# blum_SumoBRD_ECEN2440F24.net
KiCad netlist of a schematic drawn in Altium Designer
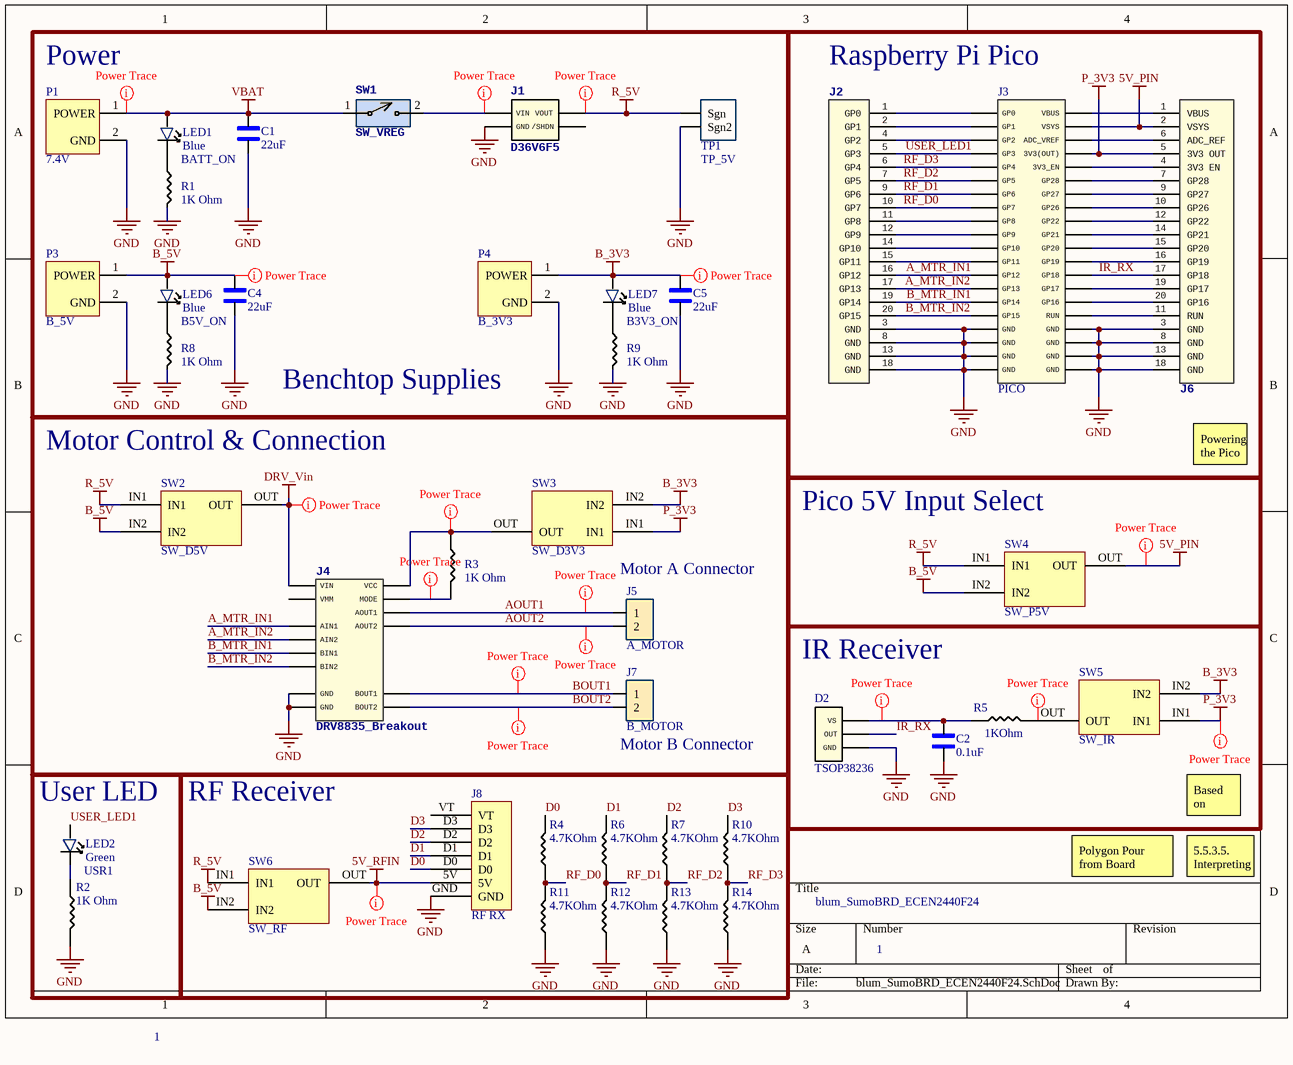
[diagram p0: blum_SumoBRD_ECEN2440F24.SchDoc]

(export (version "E")
  (design (tool "Eeschema 10.0.6"))
  (components
    (comp (ref "C1")
      (value "22uF")
      (footprint "1206_Passive_Capacitor")
      (description "22uF ±10% 25V X5R 1206 Multilayer Ceramic Capacitors MLCC - SMD/SMT RoHS")
      (fields (field (name "MFR PART #") "CL31A226KAHNNNE") (field (name "LCSC PART#") "C12891"))
      (libsource (lib "blum_SumoBRD_ECEN2440F24") (part "C_22uF_1206"))
    )
    (comp (ref "C2")
      (value "0.1uF")
      (footprint "1206_Passive_Capacitor")
      (description "MULTILAYER CERAMIC CAPACITORS MLCC - SMD/SMT 0.1UF 50V 1206 ROHS")
      (fields (field (name "MFR PART #") "CL31B104MBCNNNC") (field (name "LCSC PART#") "C730479"))
      (libsource (lib "blum_SumoBRD_ECEN2440F24") (part "C_0.1uF_1206"))
    )
    (comp (ref "C4")
      (value "22uF")
      (footprint "1206_Passive_Capacitor")
      (description "22uF ±10% 25V X5R 1206 Multilayer Ceramic Capacitors MLCC - SMD/SMT RoHS")
      (fields (field (name "MFR PART #") "CL31A226KAHNNNE") (field (name "LCSC PART#") "C12891"))
      (libsource (lib "blum_SumoBRD_ECEN2440F24") (part "C_22uF_1206"))
    )
    (comp (ref "C5")
      (value "22uF")
      (footprint "1206_Passive_Capacitor")
      (description "22uF ±10% 25V X5R 1206 Multilayer Ceramic Capacitors MLCC - SMD/SMT RoHS")
      (fields (field (name "MFR PART #") "CL31A226KAHNNNE") (field (name "LCSC PART#") "C12891"))
      (libsource (lib "blum_SumoBRD_ECEN2440F24") (part "C_22uF_1206"))
    )
    (comp (ref "D2")
      (value "TSOP38236")
      (footprint "D_TSOP38238")
      (description "IR Receiver, TSOP38236, 36 kHz")
      (libsource (lib "blum_SumoBRD_ECEN2440F24") (part "D_TSOP38238"))
    )
    (comp (ref "J1")
      (value "D36V6F5")
      (footprint "D36V6F5_JF_4")
      (description "5V, 600mA Step Down Voltage Regulator, D36V6F5. 2.54mm, P=2.54mm, Female Headers ROHS")
      (libsource (lib "blum_SumoBRD_ECEN2440F24") (part "D36V6F5_JF_4"))
    )
    (comp (ref "J2")
      (value "SAMTEC-SSQ-107-01-X-SJ")
      (footprint "JF-20-SSQ-1020-X")
      (description "2.54mm Brass Straight 1x7P 7 1 Straight,P=2.54mm  Female Headers ROHS")
      (fields (field (name "MFR PART #") "B-2200S07P-A120") (field (name "LCSC PART#") "C124418"))
      (libsource (lib "blum_SumoBRD_ECEN2440F24") (part "JF_20_PIN_FEMALE_L"))
    )
    (comp (ref "J3")
      (value "PICO")
      (footprint "RASPBERRY_PI_PICO")
      (libsource (lib "blum_SumoBRD_ECEN2440F24") (part "JF_RASPBERRY_PI_PICO"))
    )
    (comp (ref "J4")
      (value "DRV8835_Breakout")
      (footprint "JF_14_DRV8835")
      (description "Pololu DRV8835 Breakout Board\r\n2.54mm, P=2.54mm, Female Headers ROHS")
      (libsource (lib "blum_SumoBRD_ECEN2440F24") (part "DRV8835_JF_14"))
    )
    (comp (ref "J5")
      (value "A_MOTOR")
      (footprint "2_PIN_100MIL")
      (description "2.54mm Straight 2 1 Header，Breakaway Through Hole,P=2.54mm Pin Header & Female Header ROHS")
      (fields (field (name "LCSC PART#") "C124375") (field (name "MFR PART #") "B-2100S02P-A110"))
      (libsource (lib "blum_SumoBRD_ECEN2440F24") (part "JM_2_PIN_MALE"))
    )
    (comp (ref "J6")
      (value "SAMTEC-SSQ-107-01-X-SJ")
      (footprint "JF-20-SSQ-1020-X")
      (description "2.54mm Brass Straight 1x7P 7 1 Straight,P=2.54mm  Female Headers ROHS")
      (fields (field (name "MFR PART #") "B-2200S07P-A120") (field (name "LCSC PART#") "C124418"))
      (libsource (lib "blum_SumoBRD_ECEN2440F24") (part "JF_20_PIN_FEMALE_R"))
    )
    (comp (ref "J7")
      (value "B_MOTOR")
      (footprint "2_PIN_100MIL")
      (description "2.54mm Straight 2 1 Header，Breakaway Through Hole,P=2.54mm Pin Header & Female Header ROHS")
      (fields (field (name "LCSC PART#") "C124375") (field (name "MFR PART #") "B-2100S02P-A110"))
      (libsource (lib "blum_SumoBRD_ECEN2440F24") (part "JM_2_PIN_MALE_1"))
    )
    (comp (ref "J8")
      (value "RF RX")
      (footprint "JF_RF_Receiver")
      (description "RF Receiver, 7 pin")
      (libsource (lib "blum_SumoBRD_ECEN2440F24") (part "JF_RF_Receiver"))
    )
    (comp (ref "LED1")
      (value "BATT_ON")
      (footprint "LED_1206")
      (description "blue 1206  Light Emitting Diodes (LED) ROHS")
      (fields
        (field (name "MFR PART #") "NCD1206B1")
        (field (name "LCSC PART#") "C130717")
        (field (name "ALTIUM_VALUE") "Blue")
      )
      (libsource (lib "blum_SumoBRD_ECEN2440F24") (part "LED_BLUE_1206"))
    )
    (comp (ref "LED2")
      (value "USR1")
      (footprint "LED_1206")
      (description "Green 513~528nm 1206 Light Emitting Diodes (LED) RoHS")
      (fields
        (field (name "MFR PART #") "SZYY1206G")
        (field (name "LCSC PART#") "C434439")
        (field (name "ALTIUM_VALUE") "Green")
      )
      (libsource (lib "blum_SumoBRD_ECEN2440F24") (part "LED_GREEN_1206"))
    )
    (comp (ref "LED6")
      (value "B5V_ON")
      (footprint "LED_1206")
      (description "Benchtop Power Supply 5V output ON\r\nblue 1206  Light Emitting Diodes (LED) ROHS")
      (fields
        (field (name "MFR PART #") "NCD1206B1")
        (field (name "LCSC PART#") "C130717")
        (field (name "ALTIUM_VALUE") "Blue")
      )
      (libsource (lib "blum_SumoBRD_ECEN2440F24") (part "LED_BLUE_1206"))
    )
    (comp (ref "LED7")
      (value "B3V3_ON")
      (footprint "LED_1206")
      (description "Benchtop Power Supply 5V output ON\r\nblue 1206  Light Emitting Diodes (LED) ROHS")
      (fields
        (field (name "MFR PART #") "NCD1206B1")
        (field (name "LCSC PART#") "C130717")
        (field (name "ALTIUM_VALUE") "Blue")
      )
      (libsource (lib "blum_SumoBRD_ECEN2440F24") (part "LED_BLUE_1206"))
    )
    (comp (ref "P1")
      (value "7.4V")
      (footprint "P_JST_RCY")
      (description "JST RCY for LiPO battery")
      (libsource (lib "blum_SumoBRD_ECEN2440F24") (part "P_JST_RCY"))
    )
    (comp (ref "P3")
      (value "B_5V")
      (footprint "P_Terminal block 3.5mm-pitch")
      (description "Benchtop Power Supply: 5V \r\nGreen Straight pin 3.5mm  pitch; P=3.5mm  Screw terminal ROHS")
      (fields (field (name "MFR PART #") "KF350-3.5-2P") (field (name "MANUFACTURER") "Cixi Kefa Elec"))
      (libsource (lib "blum_SumoBRD_ECEN2440F24") (part "P_Terminal block"))
    )
    (comp (ref "P4")
      (value "B_3V3")
      (footprint "P_Terminal block 3.5mm-pitch")
      (description "Benchtop Power Supply: 3V3\r\nGreen Straight pin 3.5mm  pitch; P=3.5mm  Screw terminal ROHS")
      (fields (field (name "MFR PART #") "KF350-3.5-2P") (field (name "MANUFACTURER") "Cixi Kefa Elec"))
      (libsource (lib "blum_SumoBRD_ECEN2440F24") (part "P_Terminal block"))
    )
    (comp (ref "R1")
      (value "1K Ohm")
      (footprint "1206_Passive_Resitor")
      (description "CHIP RESISTOR - SURFACE MOUNT 1KOHMS ±1% 1/4W 1206 ROHS")
      (fields (field (name "MFR PART #") "RNCP1206FTD1K00CT") (field (name "LCSC PART#") "C4410"))
      (libsource (lib "blum_SumoBRD_ECEN2440F24") (part "R_1K_1206"))
    )
    (comp (ref "R2")
      (value "1K Ohm")
      (footprint "1206_Passive_Resitor")
      (description "CHIP RESISTOR - SURFACE MOUNT 1KOHMS ±1% 1/4W 1206 ROHS")
      (fields (field (name "MFR PART #") "RNCP1206FTD1K00CT") (field (name "LCSC PART#") "C4410"))
      (libsource (lib "blum_SumoBRD_ECEN2440F24") (part "R_1K_1206"))
    )
    (comp (ref "R3")
      (value "1K Ohm")
      (footprint "1206_Passive_Resitor")
      (description "CHIP RESISTOR - SURFACE MOUNT 1KOHMS ±1% 1/4W 1206 ROHS")
      (fields (field (name "MFR PART #") "RNCP1206FTD1K00CT") (field (name "LCSC PART#") "C4410"))
      (libsource (lib "blum_ECEN2440_sumo_new") (part "R_1K_1206"))
    )
    (comp (ref "R4")
      (value "4.7KOhm")
      (footprint "1206_Passive_Resitor")
      (description "4.7kΩ ±1% 0.25W ±100ppm/℃ 1206 Chip Resistor - Surface Mount RoHS")
      (fields (field (name "LCSC PART#") "C17936") (field (name "MFR PART #") "1206W4F4701T5E"))
      (libsource (lib "blum_SumoBRD_ECEN2440F24") (part "R_4.7k_1206"))
    )
    (comp (ref "R5")
      (value "1KOhm")
      (footprint "1206_Passive_Resitor")
      (description "10 kOhms ±5% 0.25W, 1/4W Chip Resistor 1206 (3216 Metric) Automotive AEC-Q200 Thick Film")
      (fields (field (name "MFR PART #") "RMCF1206FT10K0") (field (name "LCSC PART#") "C17902"))
      (libsource (lib "blum_SumoBRD_ECEN2440F24") (part "R_10KOhm_1206"))
    )
    (comp (ref "R6")
      (value "4.7KOhm")
      (footprint "1206_Passive_Resitor")
      (description "4.7kΩ ±1% 0.25W ±100ppm/℃ 1206 Chip Resistor - Surface Mount RoHS")
      (fields (field (name "LCSC PART#") "C17936") (field (name "MFR PART #") "1206W4F4701T5E"))
      (libsource (lib "blum_SumoBRD_ECEN2440F24") (part "R_4.7k_1206"))
    )
    (comp (ref "R7")
      (value "4.7KOhm")
      (footprint "1206_Passive_Resitor")
      (description "4.7kΩ ±1% 0.25W ±100ppm/℃ 1206 Chip Resistor - Surface Mount RoHS")
      (fields (field (name "LCSC PART#") "C17936") (field (name "MFR PART #") "1206W4F4701T5E"))
      (libsource (lib "blum_SumoBRD_ECEN2440F24") (part "R_4.7k_1206"))
    )
    (comp (ref "R8")
      (value "1K Ohm")
      (footprint "1206_Passive_Resitor")
      (description "CHIP RESISTOR - SURFACE MOUNT 1KOHMS ±1% 1/4W 1206 ROHS")
      (fields (field (name "MFR PART #") "RNCP1206FTD1K00CT") (field (name "LCSC PART#") "C4410"))
      (libsource (lib "blum_SumoBRD_ECEN2440F24") (part "R_1K_1206"))
    )
    (comp (ref "R9")
      (value "1K Ohm")
      (footprint "1206_Passive_Resitor")
      (description "CHIP RESISTOR - SURFACE MOUNT 1KOHMS ±1% 1/4W 1206 ROHS")
      (fields (field (name "MFR PART #") "RNCP1206FTD1K00CT") (field (name "LCSC PART#") "C4410"))
      (libsource (lib "blum_SumoBRD_ECEN2440F24") (part "R_1K_1206"))
    )
    (comp (ref "R10")
      (value "4.7KOhm")
      (footprint "1206_Passive_Resitor")
      (description "4.7kΩ ±1% 0.25W ±100ppm/℃ 1206 Chip Resistor - Surface Mount RoHS")
      (fields (field (name "LCSC PART#") "C17936") (field (name "MFR PART #") "1206W4F4701T5E"))
      (libsource (lib "blum_SumoBRD_ECEN2440F24") (part "R_4.7k_1206"))
    )
    (comp (ref "R11")
      (value "4.7KOhm")
      (footprint "1206_Passive_Resitor")
      (description "4.7kΩ ±1% 0.25W ±100ppm/℃ 1206 Chip Resistor - Surface Mount RoHS")
      (fields (field (name "LCSC PART#") "C17936") (field (name "MFR PART #") "1206W4F4701T5E"))
      (libsource (lib "blum_SumoBRD_ECEN2440F24") (part "R_4.7k_1206"))
    )
    (comp (ref "R12")
      (value "4.7KOhm")
      (footprint "1206_Passive_Resitor")
      (description "4.7kΩ ±1% 0.25W ±100ppm/℃ 1206 Chip Resistor - Surface Mount RoHS")
      (fields (field (name "LCSC PART#") "C17936") (field (name "MFR PART #") "1206W4F4701T5E"))
      (libsource (lib "blum_SumoBRD_ECEN2440F24") (part "R_4.7k_1206"))
    )
    (comp (ref "R13")
      (value "4.7KOhm")
      (footprint "1206_Passive_Resitor")
      (description "4.7kΩ ±1% 0.25W ±100ppm/℃ 1206 Chip Resistor - Surface Mount RoHS")
      (fields (field (name "LCSC PART#") "C17936") (field (name "MFR PART #") "1206W4F4701T5E"))
      (libsource (lib "blum_SumoBRD_ECEN2440F24") (part "R_4.7k_1206"))
    )
    (comp (ref "R14")
      (value "4.7KOhm")
      (footprint "1206_Passive_Resitor")
      (description "4.7kΩ ±1% 0.25W ±100ppm/℃ 1206 Chip Resistor - Surface Mount RoHS")
      (fields (field (name "LCSC PART#") "C17936") (field (name "MFR PART #") "1206W4F4701T5E"))
      (libsource (lib "blum_SumoBRD_ECEN2440F24") (part "R_4.7k_1206"))
    )
    (comp (ref "SW1")
      (value "SW_VREG")
      (footprint "2Pin-Header-Conn")
      (description "2Pin Header")
      (fields (field (name "LCSC PART#") "C124375"))
      (libsource (lib "blum_SumoBRD_ECEN2440F24") (part "SW_2Pin_100mil_Switch"))
    )
    (comp (ref "SW2")
      (value "SW_D5V")
      (footprint "3PIN_SWITCH")
      (description "3Pin Header")
      (libsource (lib "blum_SumoBRD_ECEN2440F24") (part "SW_3Pin"))
    )
    (comp (ref "SW3")
      (value "SW_D3V3")
      (footprint "3PIN_SWITCH")
      (description "3Pin Header")
      (libsource (lib "") (part "SW_3Pin_1"))
    )
    (comp (ref "SW4")
      (value "SW_P5V")
      (footprint "3PIN_SWITCH")
      (description "3Pin Header")
      (libsource (lib "blum_SumoBRD_ECEN2440F24") (part "SW_3Pin"))
    )
    (comp (ref "SW5")
      (value "SW_IR")
      (footprint "3PIN_SWITCH")
      (description "3Pin Header")
      (libsource (lib "") (part "SW_3Pin_1"))
    )
    (comp (ref "SW6")
      (value "SW_RF")
      (footprint "3PIN_SWITCH")
      (description "3Pin Header")
      (libsource (lib "blum_SumoBRD_ECEN2440F24") (part "SW_3Pin"))
    )
    (comp (ref "TP1")
      (value "TP_5V")
      (footprint "TP_Diff_Probe")
      (description "Test Point 300 mil centers")
      (libsource (lib "blum_SumoBRD_ECEN2440F24") (part "TP_Diff_Probe"))
    )
  )
  (nets
    (net (code "1") (name "/AOUT1") (class "Default")
      (node (ref "J4") (pin "6") (pinfunction "AOUT1_6") (pintype "passive"))
      (node (ref "J5") (pin "1") (pinfunction "1_1") (pintype "passive"))
    )
    (net (code "2") (name "/AOUT2") (class "Default")
      (node (ref "J4") (pin "5") (pinfunction "AOUT2_5") (pintype "passive"))
      (node (ref "J5") (pin "2") (pinfunction "2_2") (pintype "passive"))
    )
    (net (code "3") (name "/A_MTR_IN1") (class "Default")
      (node (ref "J2") (pin "16") (pinfunction "GP12_16") (pintype "passive"))
      (node (ref "J3") (pin "16") (pinfunction "GP12_16") (pintype "passive"))
      (node (ref "J4") (pin "9") (pinfunction "AIN1_9") (pintype "passive"))
    )
    (net (code "4") (name "/A_MTR_IN2") (class "Default")
      (node (ref "J2") (pin "17") (pinfunction "GP13_17") (pintype "passive"))
      (node (ref "J3") (pin "17") (pinfunction "GP13_17") (pintype "passive"))
      (node (ref "J4") (pin "10") (pinfunction "AIN2_10") (pintype "passive"))
    )
    (net (code "5") (name "/BOUT1") (class "Default")
      (node (ref "J4") (pin "4") (pinfunction "BOUT1_4") (pintype "passive"))
      (node (ref "J7") (pin "1") (pinfunction "1_1") (pintype "passive"))
    )
    (net (code "6") (name "/BOUT2") (class "Default")
      (node (ref "J4") (pin "3") (pinfunction "BOUT2_3") (pintype "passive"))
      (node (ref "J7") (pin "2") (pinfunction "2_2") (pintype "passive"))
    )
    (net (code "7") (name "/B_MTR_IN1") (class "Default")
      (node (ref "J2") (pin "19") (pinfunction "GP14_19") (pintype "passive"))
      (node (ref "J3") (pin "19") (pinfunction "GP14_19") (pintype "passive"))
      (node (ref "J4") (pin "11") (pinfunction "BIN1_11") (pintype "passive"))
    )
    (net (code "8") (name "/B_MTR_IN2") (class "Default")
      (node (ref "J2") (pin "20") (pinfunction "GP15_20") (pintype "passive"))
      (node (ref "J3") (pin "20") (pinfunction "GP15_20") (pintype "passive"))
      (node (ref "J4") (pin "12") (pinfunction "BIN2_12") (pintype "passive"))
    )
    (net (code "9") (name "/D0") (class "Default")
      (node (ref "J8") (pin "D0") (pinfunction "D0_D0") (pintype "passive"))
      (node (ref "R4") (pin "2") (pinfunction "2_2") (pintype "passive"))
    )
    (net (code "10") (name "/D1") (class "Default")
      (node (ref "J8") (pin "D1") (pinfunction "D1_D1") (pintype "passive"))
      (node (ref "R6") (pin "2") (pinfunction "2_2") (pintype "passive"))
    )
    (net (code "11") (name "/D2") (class "Default")
      (node (ref "J8") (pin "D2") (pinfunction "D2_D2") (pintype "passive"))
      (node (ref "R7") (pin "2") (pinfunction "2_2") (pintype "passive"))
    )
    (net (code "12") (name "/D3") (class "Default")
      (node (ref "J8") (pin "D3") (pinfunction "D3_D3") (pintype "passive"))
      (node (ref "R10") (pin "2") (pinfunction "2_2") (pintype "passive"))
    )
    (net (code "13") (name "/IR_RX") (class "Default")
      (node (ref "D2") (pin "D_OUT") (pinfunction "OUT_D_OUT") (pintype "passive"))
      (node (ref "J3") (pin "24") (pinfunction "GP18_24") (pintype "passive"))
      (node (ref "J6") (pin "17") (pinfunction "GP18_17") (pintype "passive"))
    )
    (net (code "14") (name "/RF_D0") (class "Default")
      (node (ref "J2") (pin "10") (pinfunction "GP7_10") (pintype "passive"))
      (node (ref "J3") (pin "10") (pinfunction "GP7_10") (pintype "passive"))
      (node (ref "R11") (pin "2") (pinfunction "2_2") (pintype "passive"))
      (node (ref "R4") (pin "1") (pinfunction "1_1") (pintype "passive"))
    )
    (net (code "15") (name "/RF_D1") (class "Default")
      (node (ref "J2") (pin "9") (pinfunction "GP6_9") (pintype "passive"))
      (node (ref "J3") (pin "9") (pinfunction "GP6_9") (pintype "passive"))
      (node (ref "R12") (pin "2") (pinfunction "2_2") (pintype "passive"))
      (node (ref "R6") (pin "1") (pinfunction "1_1") (pintype "passive"))
    )
    (net (code "16") (name "/RF_D2") (class "Default")
      (node (ref "J2") (pin "7") (pinfunction "GP5_7") (pintype "passive"))
      (node (ref "J3") (pin "7") (pinfunction "GP5_7") (pintype "passive"))
      (node (ref "R13") (pin "2") (pinfunction "2_2") (pintype "passive"))
      (node (ref "R7") (pin "1") (pinfunction "1_1") (pintype "passive"))
    )
    (net (code "17") (name "/RF_D3") (class "Default")
      (node (ref "J2") (pin "6") (pinfunction "GP4_6") (pintype "passive"))
      (node (ref "J3") (pin "6") (pinfunction "GP4_6") (pintype "passive"))
      (node (ref "R10") (pin "1") (pinfunction "1_1") (pintype "passive"))
      (node (ref "R14") (pin "2") (pinfunction "2_2") (pintype "passive"))
    )
    (net (code "18") (name "/USER_LED1") (class "Default")
      (node (ref "J2") (pin "5") (pinfunction "GP3_5") (pintype "passive"))
      (node (ref "J3") (pin "5") (pinfunction "GP3_5") (pintype "passive"))
      (node (ref "LED2") (pin "1") (pinfunction "1_1") (pintype "passive"))
    )
    (net (code "19") (name "5V_PIN") (class "Default")
      (node (ref "J3") (pin "39") (pinfunction "VSYS_39") (pintype "passive"))
      (node (ref "J6") (pin "2") (pinfunction "VSYS_2") (pintype "passive"))
      (node (ref "SW4") (pin "OUT") (pinfunction "OUT_OUT") (pintype "passive"))
    )
    (net (code "20") (name "5V_RFIN") (class "Default")
      (node (ref "J8") (pin "5V") (pinfunction "5V_5V") (pintype "passive"))
      (node (ref "SW6") (pin "OUT") (pinfunction "OUT_OUT") (pintype "passive"))
    )
    (net (code "21") (name "B_3V3") (class "Default")
      (node (ref "C5") (pin "1") (pinfunction "1_1") (pintype "passive"))
      (node (ref "LED7") (pin "1") (pinfunction "1_1") (pintype "passive"))
      (node (ref "P4") (pin "1") (pinfunction "POWER_1") (pintype "passive"))
      (node (ref "SW3") (pin "IN2") (pinfunction "IN2_IN2") (pintype "passive"))
      (node (ref "SW5") (pin "IN2") (pinfunction "IN2_IN2") (pintype "passive"))
    )
    (net (code "22") (name "B_5V") (class "Default")
      (node (ref "C4") (pin "1") (pinfunction "1_1") (pintype "passive"))
      (node (ref "LED6") (pin "1") (pinfunction "1_1") (pintype "passive"))
      (node (ref "P3") (pin "1") (pinfunction "POWER_1") (pintype "passive"))
      (node (ref "SW2") (pin "IN2") (pinfunction "IN2_IN2") (pintype "passive"))
      (node (ref "SW4") (pin "IN2") (pinfunction "IN2_IN2") (pintype "passive"))
      (node (ref "SW6") (pin "IN2") (pinfunction "IN2_IN2") (pintype "passive"))
    )
    (net (code "23") (name "DRV_Vin") (class "Default")
      (node (ref "J4") (pin "2") (pinfunction "VIN_2") (pintype "passive"))
      (node (ref "SW2") (pin "OUT") (pinfunction "OUT_OUT") (pintype "passive"))
    )
    (net (code "24") (name "GND") (class "Default")
      (node (ref "C1") (pin "2") (pinfunction "2_2") (pintype "passive"))
      (node (ref "C2") (pin "1") (pinfunction "1_1") (pintype "passive"))
      (node (ref "C4") (pin "2") (pinfunction "2_2") (pintype "passive"))
      (node (ref "C5") (pin "2") (pinfunction "2_2") (pintype "passive"))
      (node (ref "D2") (pin "D_GND") (pinfunction "GND_D_GND") (pintype "passive"))
      (node (ref "J1") (pin "REG_GND") (pinfunction "GND_REG_GND") (pintype "passive"))
      (node (ref "J2") (pin "13") (pinfunction "GND_13") (pintype "passive"))
      (node (ref "J2") (pin "18") (pinfunction "GND_18") (pintype "passive"))
      (node (ref "J2") (pin "3") (pinfunction "GND_3") (pintype "passive"))
      (node (ref "J2") (pin "8") (pinfunction "GND_8") (pintype "passive"))
      (node (ref "J3") (pin "13") (pinfunction "GND_13") (pintype "passive"))
      (node (ref "J3") (pin "18") (pinfunction "GND_18") (pintype "passive"))
      (node (ref "J3") (pin "23") (pinfunction "GND_23") (pintype "passive"))
      (node (ref "J3") (pin "28") (pinfunction "GND_28") (pintype "passive"))
      (node (ref "J3") (pin "3") (pinfunction "GND_3") (pintype "passive"))
      (node (ref "J3") (pin "33") (pinfunction "GND_33") (pintype "passive"))
      (node (ref "J3") (pin "38") (pinfunction "GND_38") (pintype "passive"))
      (node (ref "J3") (pin "8") (pinfunction "GND_8") (pintype "passive"))
      (node (ref "J4") (pin "1") (pinfunction "GND_1") (pintype "passive"))
      (node (ref "J4") (pin "14") (pinfunction "GND_14") (pintype "passive"))
      (node (ref "J6") (pin "13") (pinfunction "GND_13") (pintype "passive"))
      (node (ref "J6") (pin "18") (pinfunction "GND_18") (pintype "passive"))
      (node (ref "J6") (pin "3") (pinfunction "GND_3") (pintype "passive"))
      (node (ref "J6") (pin "8") (pinfunction "GND_8") (pintype "passive"))
      (node (ref "J8") (pin "GND") (pinfunction "GND_GND") (pintype "passive"))
      (node (ref "P1") (pin "2") (pinfunction "GND_2") (pintype "passive"))
      (node (ref "P3") (pin "2") (pinfunction "GND_2") (pintype "passive"))
      (node (ref "P4") (pin "2") (pinfunction "GND_2") (pintype "passive"))
      (node (ref "R1") (pin "2") (pinfunction "2_2") (pintype "passive"))
      (node (ref "R11") (pin "1") (pinfunction "1_1") (pintype "passive"))
      (node (ref "R12") (pin "1") (pinfunction "1_1") (pintype "passive"))
      (node (ref "R13") (pin "1") (pinfunction "1_1") (pintype "passive"))
      (node (ref "R14") (pin "1") (pinfunction "1_1") (pintype "passive"))
      (node (ref "R2") (pin "2") (pinfunction "2_2") (pintype "passive"))
      (node (ref "R8") (pin "2") (pinfunction "2_2") (pintype "passive"))
      (node (ref "R9") (pin "2") (pinfunction "2_2") (pintype "passive"))
      (node (ref "TP1") (pin "2") (pinfunction "Sgn2_2") (pintype "passive"))
    )
    (net (code "25") (name "Net-(D2-VS)") (class "Default")
      (node (ref "C2") (pin "2") (pinfunction "2_2") (pintype "passive"))
      (node (ref "D2") (pin "D_VS") (pinfunction "VS_D_VS") (pintype "passive"))
      (node (ref "R5") (pin "1") (pinfunction "1_1") (pintype "passive"))
    )
    (net (code "26") (name "Net-(J1-VIN)") (class "Default")
      (node (ref "J1") (pin "REG_VIN") (pinfunction "VIN_REG_VIN") (pintype "passive"))
      (node (ref "SW1") (pin "2") (pinfunction "2_2") (pintype "passive"))
    )
    (net (code "27") (name "Net-(J2-GP0)") (class "Default")
      (node (ref "J2") (pin "1") (pinfunction "GP0_1") (pintype "passive"))
      (node (ref "J3") (pin "1") (pinfunction "GP0_1") (pintype "passive"))
    )
    (net (code "28") (name "Net-(J2-GP1)") (class "Default")
      (node (ref "J2") (pin "2") (pinfunction "GP1_2") (pintype "passive"))
      (node (ref "J3") (pin "2") (pinfunction "GP1_2") (pintype "passive"))
    )
    (net (code "29") (name "Net-(J2-GP2)") (class "Default")
      (node (ref "J2") (pin "4") (pinfunction "GP2_4") (pintype "passive"))
      (node (ref "J3") (pin "4") (pinfunction "GP2_4") (pintype "passive"))
    )
    (net (code "30") (name "Net-(J2-GP8)") (class "Default")
      (node (ref "J2") (pin "11") (pinfunction "GP8_11") (pintype "passive"))
      (node (ref "J3") (pin "11") (pinfunction "GP8_11") (pintype "passive"))
    )
    (net (code "31") (name "Net-(J2-GP9)") (class "Default")
      (node (ref "J2") (pin "12") (pinfunction "GP9_12") (pintype "passive"))
      (node (ref "J3") (pin "12") (pinfunction "GP9_12") (pintype "passive"))
    )
    (net (code "32") (name "Net-(J2-GP10)") (class "Default")
      (node (ref "J2") (pin "14") (pinfunction "GP10_14") (pintype "passive"))
      (node (ref "J3") (pin "14") (pinfunction "GP10_14") (pintype "passive"))
    )
    (net (code "33") (name "Net-(J2-GP11)") (class "Default")
      (node (ref "J2") (pin "15") (pinfunction "GP11_15") (pintype "passive"))
      (node (ref "J3") (pin "15") (pinfunction "GP11_15") (pintype "passive"))
    )
    (net (code "34") (name "Net-(J3-3V3_EN)") (class "Default")
      (node (ref "J3") (pin "37") (pinfunction "3V3_EN_37") (pintype "passive"))
      (node (ref "J6") (pin "4") (pinfunction "3V3_EN_4") (pintype "passive"))
    )
    (net (code "35") (name "Net-(J3-ADC_VREF)") (class "Default")
      (node (ref "J3") (pin "35") (pinfunction "ADC_VREF_35") (pintype "passive"))
      (node (ref "J6") (pin "6") (pinfunction "ADC_REF_6") (pintype "passive"))
    )
    (net (code "36") (name "Net-(J3-GP16)") (class "Default")
      (node (ref "J3") (pin "21") (pinfunction "GP16_21") (pintype "passive"))
      (node (ref "J6") (pin "20") (pinfunction "GP16_20") (pintype "passive"))
    )
    (net (code "37") (name "Net-(J3-GP17)") (class "Default")
      (node (ref "J3") (pin "22") (pinfunction "GP17_22") (pintype "passive"))
      (node (ref "J6") (pin "19") (pinfunction "GP17_19") (pintype "passive"))
    )
    (net (code "38") (name "Net-(J3-GP19)") (class "Default")
      (node (ref "J3") (pin "25") (pinfunction "GP19_25") (pintype "passive"))
      (node (ref "J6") (pin "16") (pinfunction "GP19_16") (pintype "passive"))
    )
    (net (code "39") (name "Net-(J3-GP20)") (class "Default")
      (node (ref "J3") (pin "26") (pinfunction "GP20_26") (pintype "passive"))
      (node (ref "J6") (pin "15") (pinfunction "GP20_15") (pintype "passive"))
    )
    (net (code "40") (name "Net-(J3-GP21)") (class "Default")
      (node (ref "J3") (pin "27") (pinfunction "GP21_27") (pintype "passive"))
      (node (ref "J6") (pin "14") (pinfunction "GP21_14") (pintype "passive"))
    )
    (net (code "41") (name "Net-(J3-GP22)") (class "Default")
      (node (ref "J3") (pin "29") (pinfunction "GP22_29") (pintype "passive"))
      (node (ref "J6") (pin "12") (pinfunction "GP22_12") (pintype "passive"))
    )
    (net (code "42") (name "Net-(J3-GP26)") (class "Default")
      (node (ref "J3") (pin "31") (pinfunction "GP26_31") (pintype "passive"))
      (node (ref "J6") (pin "10") (pinfunction "GP26_10") (pintype "passive"))
    )
    (net (code "43") (name "Net-(J3-GP27)") (class "Default")
      (node (ref "J3") (pin "32") (pinfunction "GP27_32") (pintype "passive"))
      (node (ref "J6") (pin "9") (pinfunction "GP27_9") (pintype "passive"))
    )
    (net (code "44") (name "Net-(J3-GP28)") (class "Default")
      (node (ref "J3") (pin "34") (pinfunction "GP28_34") (pintype "passive"))
      (node (ref "J6") (pin "7") (pinfunction "GP28_7") (pintype "passive"))
    )
    (net (code "45") (name "Net-(J3-RUN)") (class "Default")
      (node (ref "J3") (pin "30") (pinfunction "RUN_30") (pintype "passive"))
      (node (ref "J6") (pin "11") (pinfunction "RUN_11") (pintype "passive"))
    )
    (net (code "46") (name "Net-(J3-VBUS)") (class "Default")
      (node (ref "J3") (pin "40") (pinfunction "VBUS_40") (pintype "passive"))
      (node (ref "J6") (pin "1") (pinfunction "VBUS_1") (pintype "passive"))
    )
    (net (code "47") (name "Net-(J4-MODE)") (class "Default")
      (node (ref "J4") (pin "8") (pinfunction "MODE_8") (pintype "passive"))
      (node (ref "R3") (pin "2") (pinfunction "2_2") (pintype "passive"))
    )
    (net (code "48") (name "Net-(J4-VCC)") (class "Default")
      (node (ref "J4") (pin "13") (pinfunction "VCC_13") (pintype "passive"))
      (node (ref "R3") (pin "1") (pinfunction "1_1") (pintype "passive"))
      (node (ref "SW3") (pin "OUT") (pinfunction "OUT_OUT") (pintype "passive"))
    )
    (net (code "49") (name "Net-(LED1-Pad2)") (class "Default")
      (node (ref "LED1") (pin "2") (pinfunction "2_2") (pintype "passive"))
      (node (ref "R1") (pin "1") (pinfunction "1_1") (pintype "passive"))
    )
    (net (code "50") (name "Net-(LED2-Pad2)") (class "Default")
      (node (ref "LED2") (pin "2") (pinfunction "2_2") (pintype "passive"))
      (node (ref "R2") (pin "1") (pinfunction "1_1") (pintype "passive"))
    )
    (net (code "51") (name "Net-(LED6-Pad2)") (class "Default")
      (node (ref "LED6") (pin "2") (pinfunction "2_2") (pintype "passive"))
      (node (ref "R8") (pin "1") (pinfunction "1_1") (pintype "passive"))
    )
    (net (code "52") (name "Net-(LED7-Pad2)") (class "Default")
      (node (ref "LED7") (pin "2") (pinfunction "2_2") (pintype "passive"))
      (node (ref "R9") (pin "1") (pinfunction "1_1") (pintype "passive"))
    )
    (net (code "53") (name "Net-(R5-Pad2)") (class "Default")
      (node (ref "R5") (pin "2") (pinfunction "2_2") (pintype "passive"))
      (node (ref "SW5") (pin "OUT") (pinfunction "OUT_OUT") (pintype "passive"))
    )
    (net (code "54") (name "P_3V3") (class "Default")
      (node (ref "J3") (pin "36") (pinfunction "3V3(OUT)_36") (pintype "passive"))
      (node (ref "J6") (pin "5") (pinfunction "3V3_OUT_5") (pintype "passive"))
      (node (ref "SW3") (pin "IN1") (pinfunction "IN1_IN1") (pintype "passive"))
      (node (ref "SW5") (pin "IN1") (pinfunction "IN1_IN1") (pintype "passive"))
    )
    (net (code "55") (name "R_5V") (class "Default")
      (node (ref "J1") (pin "REG_VOUT") (pinfunction "VOUT_REG_VOUT") (pintype "passive"))
      (node (ref "SW2") (pin "IN1") (pinfunction "IN1_IN1") (pintype "passive"))
      (node (ref "SW4") (pin "IN1") (pinfunction "IN1_IN1") (pintype "passive"))
      (node (ref "SW6") (pin "IN1") (pinfunction "IN1_IN1") (pintype "passive"))
      (node (ref "TP1") (pin "1") (pinfunction "Sgn_1") (pintype "passive"))
    )
    (net (code "56") (name "VBAT") (class "Default")
      (node (ref "C1") (pin "1") (pinfunction "1_1") (pintype "passive"))
      (node (ref "LED1") (pin "1") (pinfunction "1_1") (pintype "passive"))
      (node (ref "P1") (pin "1") (pinfunction "POWER_1") (pintype "passive"))
      (node (ref "SW1") (pin "1") (pinfunction "1_1") (pintype "passive"))
    )
    (net (code "57") (name "unconnected-(J1-{slash}SHDN-PadREG_SHDN)") (class "Default")
      (node (ref "J1") (pin "REG_SHDN") (pinfunction "/SHDN_REG_SHDN") (pintype "passive"))
    )
    (net (code "58") (name "unconnected-(J4-VMM-Pad7)") (class "Default")
      (node (ref "J4") (pin "7") (pinfunction "VMM_7") (pintype "passive"))
    )
    (net (code "59") (name "unconnected-(J8-PadVT)") (class "Default")
      (node (ref "J8") (pin "VT") (pinfunction "VT_VT") (pintype "passive"))
    )
  )
)
